# Sheet_v1.net
KiCad netlist of a schematic drawn in Altium Designer
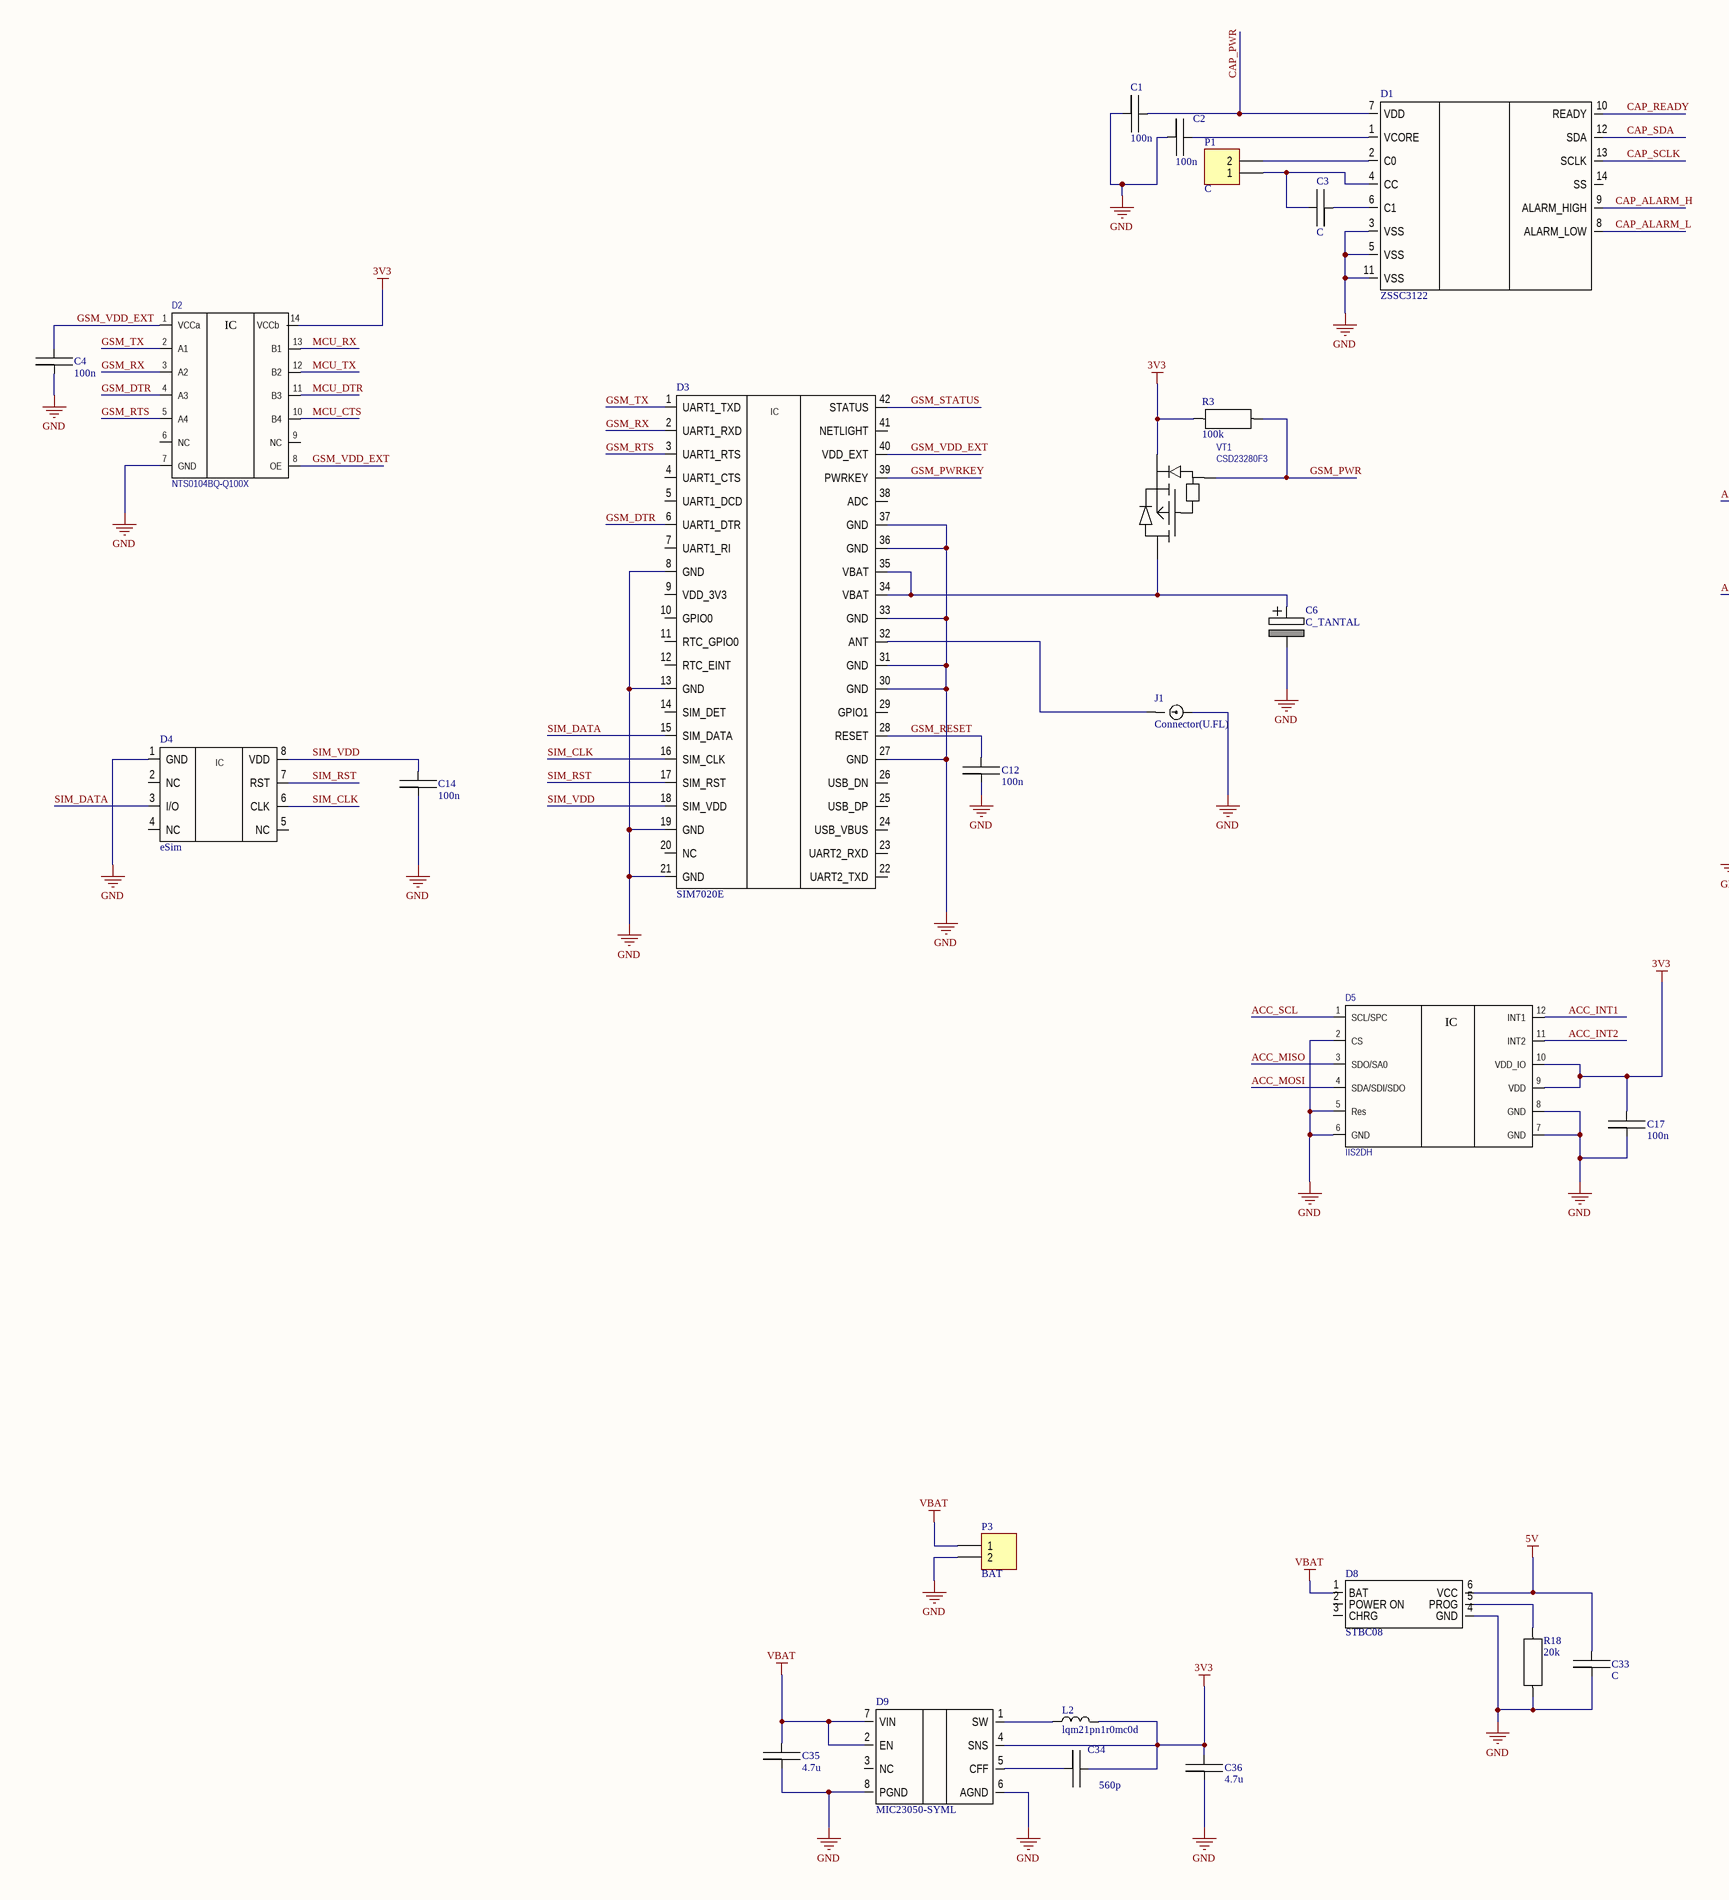
[diagram p0: Sheet_v1.SchDoc, left]
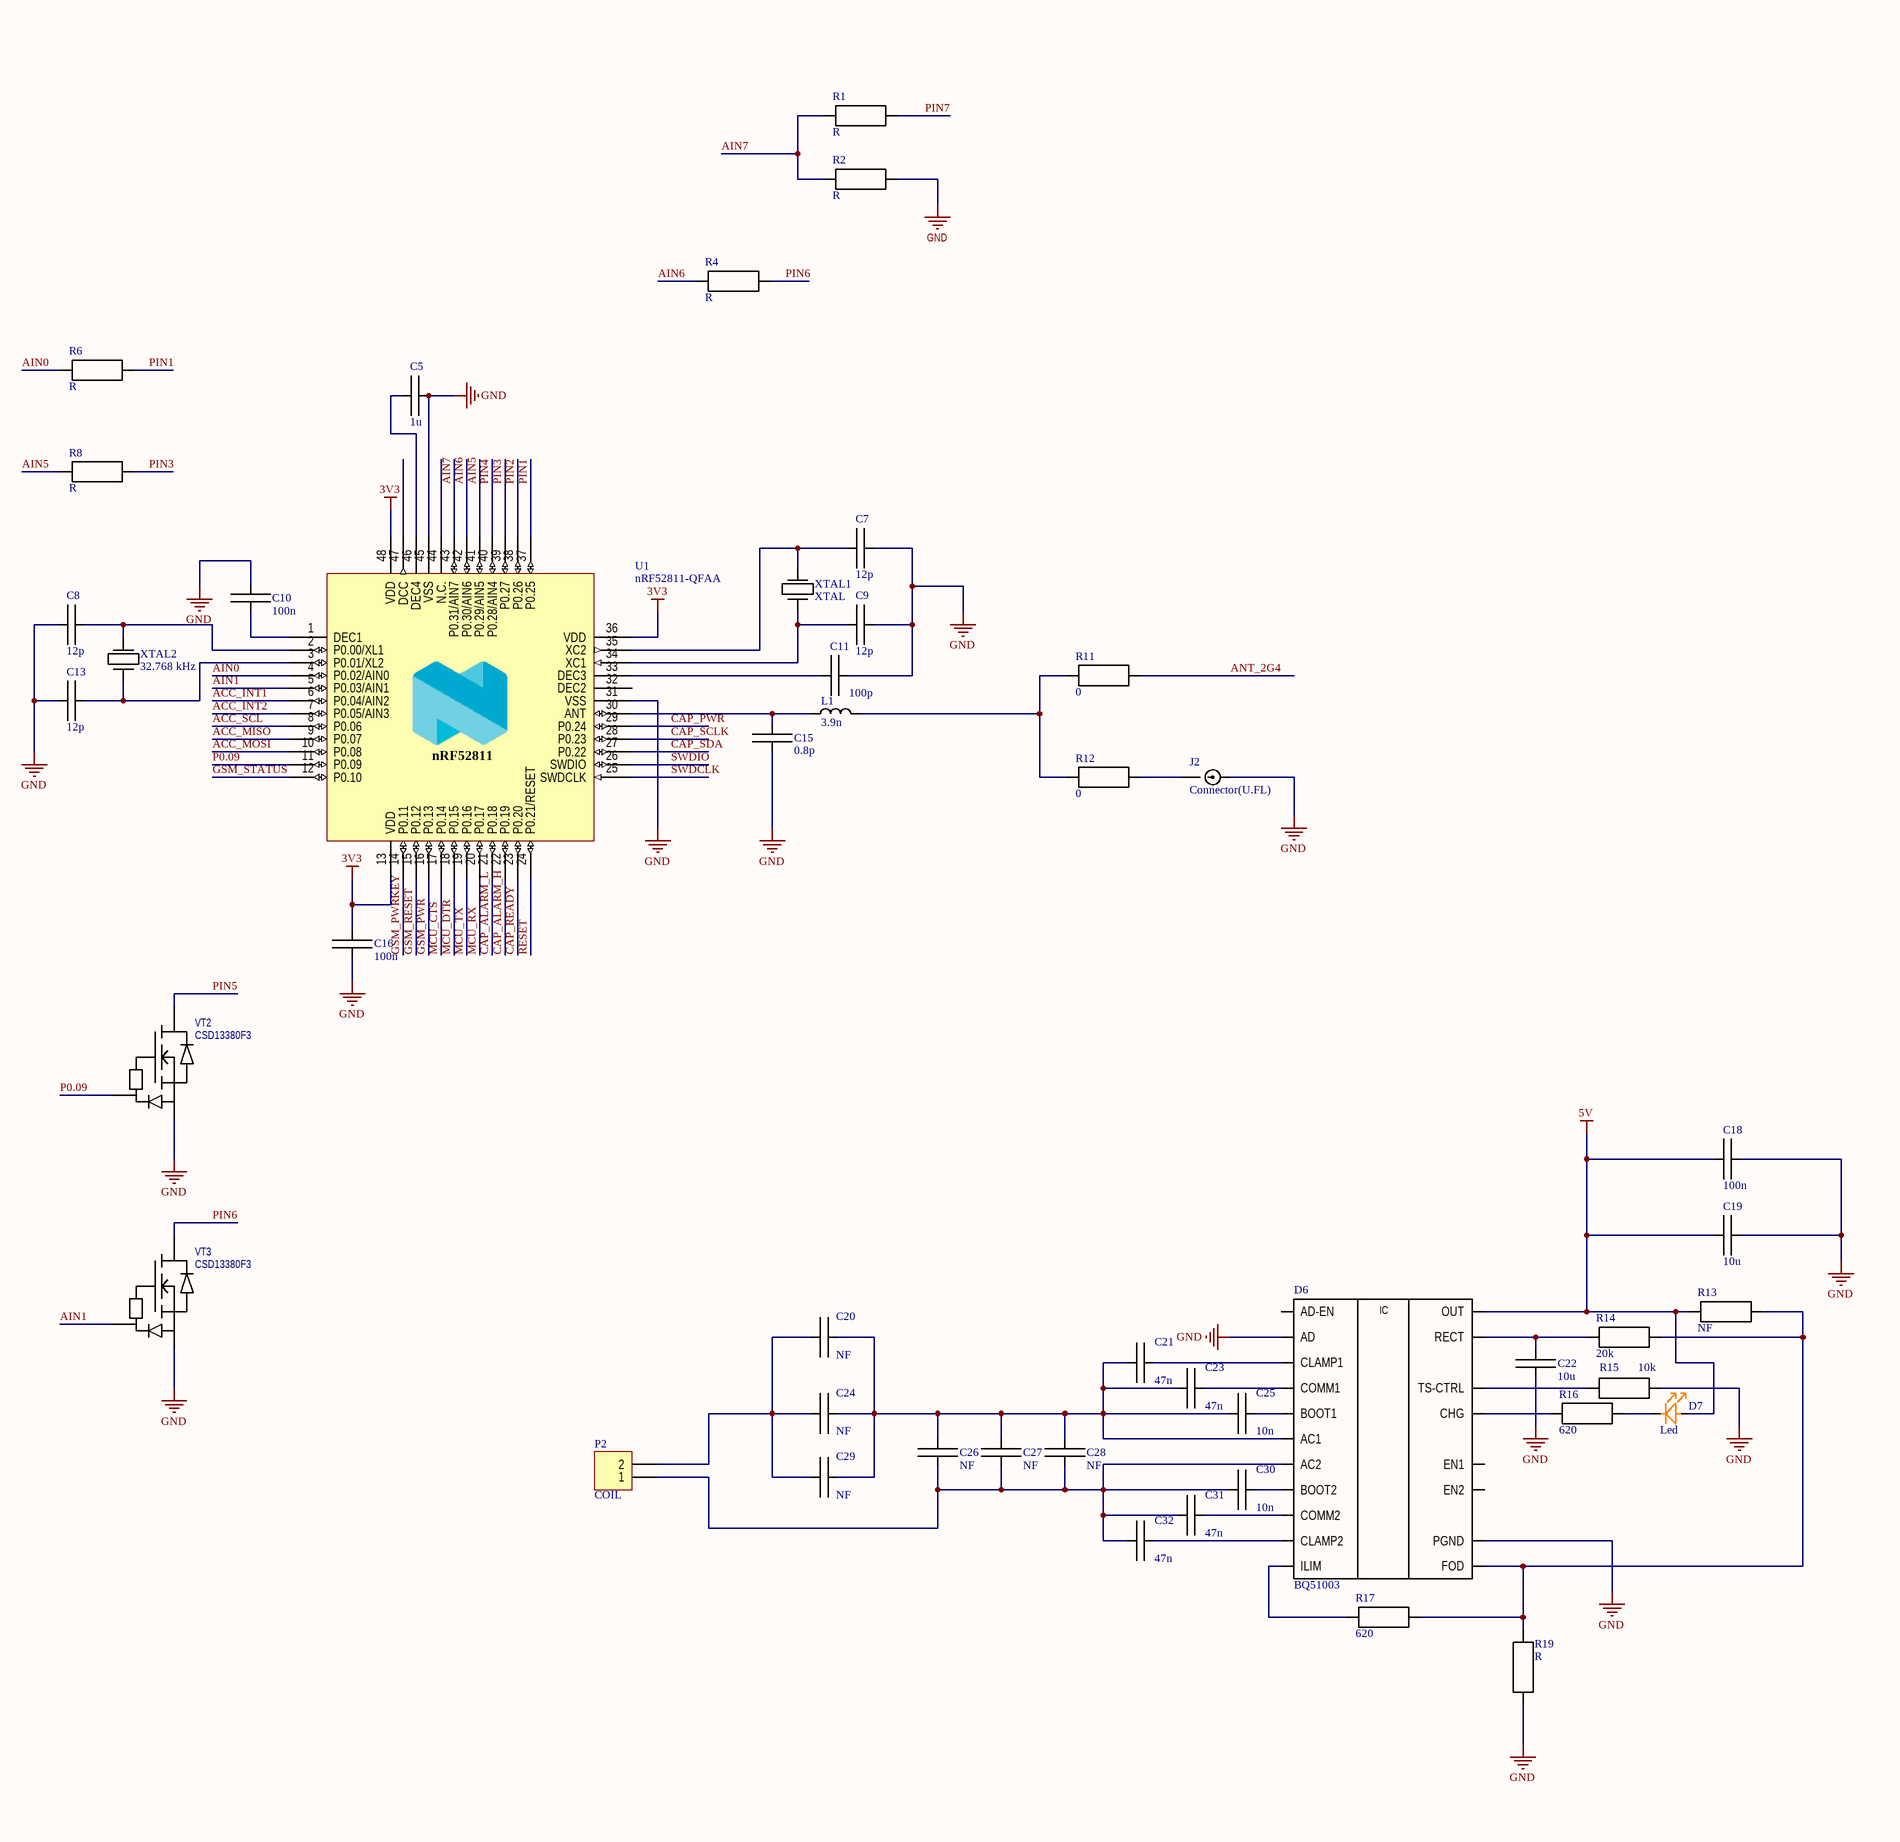
[diagram p1: Sheet_v1.SchDoc, right]

(export (version "E")
  (design (tool "Eeschema 10.0.6"))
  (components
    (comp (ref "C1") (value "100n") (footprint "C0402") (libsource (lib "Schlib1") (part "C")))
    (comp (ref "C2") (value "100n") (footprint "C0402") (libsource (lib "Schlib1") (part "C")))
    (comp (ref "C3") (value "C") (footprint "C0402") (libsource (lib "Schlib1") (part "C")))
    (comp (ref "C4") (value "100n") (footprint "C0402") (libsource (lib "Schlib1") (part "C")))
    (comp (ref "C5") (value "1u") (footprint "C0402") (libsource (lib "Schlib1") (part "C")))
    (comp (ref "C6") (value "C_TANTAL") (footprint "C_TYPE_D") (libsource (lib "Schlib1") (part "C_TANTAL")))
    (comp (ref "C7") (value "12p") (footprint "C0402") (libsource (lib "Schlib1") (part "C")))
    (comp (ref "C8") (value "12p") (footprint "C0402") (libsource (lib "Schlib1") (part "C")))
    (comp (ref "C9") (value "12p") (footprint "C0402") (libsource (lib "Schlib1") (part "C")))
    (comp (ref "C10") (value "100n") (footprint "C0402") (libsource (lib "Schlib1") (part "C")))
    (comp (ref "C11") (value "100p") (footprint "C0402") (libsource (lib "Schlib1") (part "C")))
    (comp (ref "C12") (value "100n") (footprint "C0402") (libsource (lib "Schlib1") (part "C")))
    (comp (ref "C13") (value "12p") (footprint "C0402") (libsource (lib "Schlib1") (part "C")))
    (comp (ref "C14") (value "100n") (footprint "C0402") (libsource (lib "Schlib1") (part "C")))
    (comp (ref "C15") (value "0.8p") (footprint "C0402") (libsource (lib "Schlib1") (part "C")))
    (comp (ref "C16") (value "100n") (footprint "C0402") (libsource (lib "Schlib1") (part "C")))
    (comp (ref "C17") (value "100n") (footprint "C0402") (libsource (lib "Schlib1") (part "C")))
    (comp (ref "C18") (value "100n") (footprint "C0402") (libsource (lib "Schlib1") (part "C")))
    (comp (ref "C19") (value "10u") (footprint "C0603") (libsource (lib "Schlib1") (part "C")))
    (comp (ref "C20") (value "NF") (footprint "C0603") (libsource (lib "Schlib1") (part "C")))
    (comp (ref "C21") (value "47n") (footprint "C0603") (libsource (lib "Schlib1") (part "C")))
    (comp (ref "C22") (value "10u") (footprint "C0402") (libsource (lib "Schlib1") (part "C")))
    (comp (ref "C23") (value "47n") (footprint "C0603") (libsource (lib "Schlib1") (part "C")))
    (comp (ref "C24") (value "NF") (footprint "C0603") (libsource (lib "Schlib1") (part "C")))
    (comp (ref "C25") (value "10n") (footprint "C0603") (libsource (lib "Schlib1") (part "C")))
    (comp (ref "C26") (value "NF") (footprint "C0603") (libsource (lib "Schlib1") (part "C")))
    (comp (ref "C27") (value "NF") (footprint "C0603") (libsource (lib "Schlib1") (part "C")))
    (comp (ref "C28") (value "NF") (footprint "C0603") (libsource (lib "Schlib1") (part "C")))
    (comp (ref "C29") (value "NF") (footprint "C0603") (libsource (lib "Schlib1") (part "C")))
    (comp (ref "C30") (value "10n") (footprint "C0603") (libsource (lib "Schlib1") (part "C")))
    (comp (ref "C31") (value "47n") (footprint "C0603") (libsource (lib "Schlib1") (part "C")))
    (comp (ref "C32") (value "47n") (footprint "C0603") (libsource (lib "Schlib1") (part "C")))
    (comp (ref "C33") (value "C") (footprint "C0402") (libsource (lib "Schlib1") (part "C")))
    (comp (ref "C34") (value "560p") (footprint "C0402") (libsource (lib "Schlib1") (part "C")))
    (comp (ref "C35") (value "4.7u") (footprint "C0805") (libsource (lib "Schlib1") (part "C")))
    (comp (ref "C36") (value "4.7u") (footprint "C0805") (libsource (lib "Schlib1") (part "C")))
    (comp (ref "D1") (value "ZSSC3122") (footprint "TSSOP14") (libsource (lib "Schlib1") (part "ZSSC3122")))
    (comp (ref "D2")
      (value "NTS0104BQ-Q100X")
      (footprint "DHVQFN14")
      (libsource (lib "Schlib1") (part "NTS0304"))
    )
    (comp (ref "D3") (value "SIM7020E") (footprint "SIM7020E") (libsource (lib "Schlib1") (part "SIM7020E")))
    (comp (ref "D4") (value "eSim") (footprint "VQFN8") (libsource (lib "Schlib1") (part "eSim")))
    (comp (ref "D5") (value "IIS2DH") (footprint "LGA12") (libsource (lib "Schlib1") (part "IIS2DH")))
    (comp (ref "D6") (value "BQ51003") (footprint "DSBGA") (libsource (lib "Schlib1") (part "BQ51003")))
    (comp (ref "D7") (value "Led") (footprint "D0402(1006)") (libsource (lib "Schlib1") (part "Led")))
    (comp (ref "D8") (value "STBC08") (footprint "DFN6") (libsource (lib "Schlib1") (part "STBC08")))
    (comp (ref "D9")
      (value "MIC23050-SYML")
      (footprint "MLF8")
      (libsource (lib "Schlib1") (part "MIC23050-SYML"))
    )
    (comp (ref "J1")
      (value "Connector(U.FL)")
      (footprint "U.FL")
      (libsource (lib "Schlib1") (part "Connector(U.FL)"))
    )
    (comp (ref "J2")
      (value "Connector(U.FL)")
      (footprint "U.FL")
      (libsource (lib "Schlib1") (part "Connector(U.FL)"))
    )
    (comp (ref "L1") (value "3.9n") (footprint "L0402") (libsource (lib "Schlib1") (part "L")))
    (comp (ref "L2") (value "lqm21pn1r0mc0d") (footprint "L0805") (libsource (lib "Schlib1") (part "L")))
    (comp (ref "P1")
      (value "C")
      (footprint "HDR1X2")
      (description "Header, 2-Pin")
      (fields (field (name "PUBLISHER") "Altium Limited"))
      (libsource (lib "Miscellaneous Connectors") (part "Header 2"))
    )
    (comp (ref "P2")
      (value "COIL")
      (footprint "HDR1X2")
      (description "Header, 2-Pin")
      (fields (field (name "PUBLISHER") "Altium Limited"))
      (libsource (lib "Miscellaneous Connectors") (part "Header 2"))
    )
    (comp (ref "P3")
      (value "BAT")
      (footprint "HDR1X2")
      (description "Header, 2-Pin")
      (fields (field (name "PUBLISHER") "Altium Limited"))
      (libsource (lib "") (part "Header 2_1"))
    )
    (comp (ref "R1") (value "R") (footprint "R0402") (libsource (lib "Schlib1") (part "R")))
    (comp (ref "R2") (value "R") (footprint "R0402") (libsource (lib "Schlib1") (part "R")))
    (comp (ref "R3") (value "100k") (footprint "R0402") (libsource (lib "Schlib1") (part "R")))
    (comp (ref "R4") (value "R") (footprint "R0402") (libsource (lib "Schlib1") (part "R")))
    (comp (ref "R6") (value "R") (footprint "R0402") (libsource (lib "Schlib1") (part "R")))
    (comp (ref "R8") (value "R") (footprint "R0402") (libsource (lib "Schlib1") (part "R")))
    (comp (ref "R11") (value "0") (footprint "R0402") (libsource (lib "Schlib1") (part "R")))
    (comp (ref "R12") (value "0") (footprint "R0402") (libsource (lib "Schlib1") (part "R")))
    (comp (ref "R13") (value "NF") (footprint "R0402") (libsource (lib "Schlib1") (part "R")))
    (comp (ref "R14") (value "20k") (footprint "R0402") (libsource (lib "Schlib1") (part "R")))
    (comp (ref "R15") (value "10k") (footprint "R0402") (libsource (lib "Schlib1") (part "R")))
    (comp (ref "R16") (value "620") (footprint "R0402") (libsource (lib "Schlib1") (part "R")))
    (comp (ref "R17") (value "620") (footprint "R0402") (libsource (lib "Schlib1") (part "R")))
    (comp (ref "R18") (value "20k") (footprint "R0402") (libsource (lib "Schlib1") (part "R")))
    (comp (ref "R19") (value "R") (footprint "R0402") (libsource (lib "Schlib1") (part "R")))
    (comp (ref "U1")
      (value "nRF52811-QFAA")
      (footprint "QFN40P600X600X90-48N")
      (description "Multi-protocol Bluetooth Low Energy, IEEE 802.15.4, ANT and 2.4GHz proprietary system-on-chip")
      (fields
        (field (name "PART NUMBER") "nRF52811-QFAAA0")
        (field (name "MANUFACTURER") "Nordic Semiconductor")
        (field (name "PUBLISHER") "Nordic Semiconductor")
      )
      (libsource (lib "nrf52811_qxaa") (part "nRF52811_QFAA"))
    )
    (comp (ref "VT1")
      (value "CSD23280F3")
      (footprint "CSD13380F3")
      (libsource (lib "Schlib1") (part "CSD23280F3"))
    )
    (comp (ref "VT2")
      (value "CSD13380F3")
      (footprint "CSD13380F3")
      (libsource (lib "Schlib1") (part "CSD13380F3"))
    )
    (comp (ref "VT3")
      (value "CSD13380F3")
      (footprint "CSD13380F3")
      (libsource (lib "Schlib1") (part "CSD13380F3"))
    )
    (comp (ref "XTAL1") (value "XTAL") (footprint "NX2016SA") (libsource (lib "Schlib1") (part "XTAL")))
    (comp (ref "XTAL2")
      (value "32.768 kHz")
      (footprint "NX2012SA")
      (libsource (lib "Schlib1") (part "32.768 kHz"))
    )
  )
  (nets
    (net (code "1") (name "/ACC_INT1") (class "Default")
      (node (ref "D5") (pin "12") (pinfunction "INT1_12") (pintype "passive"))
      (node (ref "U1") (pin "6") (pinfunction "P0.04/AIN2_6") (pintype "bidirectional"))
    )
    (net (code "2") (name "/ACC_INT2") (class "Default")
      (node (ref "D5") (pin "11") (pinfunction "INT2_11") (pintype "passive"))
      (node (ref "U1") (pin "7") (pinfunction "P0.05/AIN3_7") (pintype "bidirectional"))
    )
    (net (code "3") (name "/ACC_MISO") (class "Default")
      (node (ref "D5") (pin "3") (pinfunction "SDO/SA0_3") (pintype "passive"))
      (node (ref "U1") (pin "9") (pinfunction "P0.07_9") (pintype "bidirectional"))
    )
    (net (code "4") (name "/ACC_MOSI") (class "Default")
      (node (ref "D5") (pin "4") (pinfunction "SDA/SDI/SDO_4") (pintype "passive"))
      (node (ref "U1") (pin "10") (pinfunction "P0.08_10") (pintype "bidirectional"))
    )
    (net (code "5") (name "/ACC_SCL") (class "Default")
      (node (ref "D5") (pin "1") (pinfunction "SCL/SPC_1") (pintype "passive"))
      (node (ref "U1") (pin "8") (pinfunction "P0.06_8") (pintype "bidirectional"))
    )
    (net (code "6") (name "/AIN0") (class "Default")
      (node (ref "R6") (pin "1") (pinfunction "1_1") (pintype "passive"))
      (node (ref "U1") (pin "4") (pinfunction "P0.02/AIN0_4") (pintype "bidirectional"))
    )
    (net (code "7") (name "/AIN1") (class "Default")
      (node (ref "U1") (pin "5") (pinfunction "P0.03/AIN1_5") (pintype "bidirectional"))
      (node (ref "VT3") (pin "G") (pinfunction "G_G") (pintype "passive"))
    )
    (net (code "8") (name "/AIN5") (class "Default")
      (node (ref "R8") (pin "1") (pinfunction "1_1") (pintype "passive"))
      (node (ref "U1") (pin "41") (pinfunction "P0.29/AIN5_41") (pintype "bidirectional"))
    )
    (net (code "9") (name "/AIN6") (class "Default")
      (node (ref "R4") (pin "1") (pinfunction "1_1") (pintype "passive"))
      (node (ref "U1") (pin "42") (pinfunction "P0.30/AIN6_42") (pintype "bidirectional"))
    )
    (net (code "10") (name "/AIN7") (class "Default")
      (node (ref "R1") (pin "1") (pinfunction "1_1") (pintype "passive"))
      (node (ref "R2") (pin "1") (pinfunction "1_1") (pintype "passive"))
      (node (ref "U1") (pin "43") (pinfunction "P0.31/AIN7_43") (pintype "bidirectional"))
    )
    (net (code "11") (name "/ANT_2G4") (class "Default")
      (node (ref "R11") (pin "2") (pinfunction "2_2") (pintype "passive"))
    )
    (net (code "12") (name "/CAP_ALARM_H") (class "Default")
      (node (ref "D1") (pin "9") (pinfunction "ALARM_HIGH_9") (pintype "passive"))
      (node (ref "U1") (pin "22") (pinfunction "P0.19_22") (pintype "bidirectional"))
    )
    (net (code "13") (name "/CAP_ALARM_L") (class "Default")
      (node (ref "D1") (pin "8") (pinfunction "ALARM_LOW_8") (pintype "passive"))
      (node (ref "U1") (pin "21") (pinfunction "P0.18_21") (pintype "bidirectional"))
    )
    (net (code "14") (name "/CAP_PWR") (class "Default")
      (node (ref "C1") (pin "2") (pinfunction "2_2") (pintype "passive"))
      (node (ref "D1") (pin "7") (pinfunction "VDD_7") (pintype "passive"))
      (node (ref "U1") (pin "29") (pinfunction "P0.24_29") (pintype "bidirectional"))
    )
    (net (code "15") (name "/CAP_READY") (class "Default")
      (node (ref "D1") (pin "10") (pinfunction "READY_10") (pintype "passive"))
      (node (ref "U1") (pin "23") (pinfunction "P0.20_23") (pintype "bidirectional"))
    )
    (net (code "16") (name "/CAP_SCLK") (class "Default")
      (node (ref "D1") (pin "13") (pinfunction "SCLK_13") (pintype "passive"))
      (node (ref "U1") (pin "28") (pinfunction "P0.23_28") (pintype "bidirectional"))
    )
    (net (code "17") (name "/CAP_SDA") (class "Default")
      (node (ref "D1") (pin "12") (pinfunction "SDA_12") (pintype "passive"))
      (node (ref "U1") (pin "27") (pinfunction "P0.22_27") (pintype "bidirectional"))
    )
    (net (code "18") (name "/GSM_DTR") (class "Default")
      (node (ref "D2") (pin "4") (pinfunction "A3_4") (pintype "passive"))
      (node (ref "D3") (pin "6") (pinfunction "UART1_DTR_6") (pintype "passive"))
    )
    (net (code "19") (name "/GSM_PWR") (class "Default")
      (node (ref "R3") (pin "2") (pinfunction "2_2") (pintype "passive"))
      (node (ref "U1") (pin "16") (pinfunction "P0.13_16") (pintype "bidirectional"))
      (node (ref "VT1") (pin "G") (pinfunction "G_G") (pintype "passive"))
    )
    (net (code "20") (name "/GSM_PWRKEY") (class "Default")
      (node (ref "D3") (pin "39") (pinfunction "PWRKEY_39") (pintype "passive"))
      (node (ref "U1") (pin "14") (pinfunction "P0.11_14") (pintype "bidirectional"))
    )
    (net (code "21") (name "/GSM_RESET") (class "Default")
      (node (ref "C12") (pin "2") (pinfunction "2_2") (pintype "passive"))
      (node (ref "D3") (pin "28") (pinfunction "RESET_28") (pintype "passive"))
      (node (ref "U1") (pin "15") (pinfunction "P0.12_15") (pintype "bidirectional"))
    )
    (net (code "22") (name "/GSM_RTS") (class "Default")
      (node (ref "D2") (pin "5") (pinfunction "A4_5") (pintype "passive"))
      (node (ref "D3") (pin "3") (pinfunction "UART1_RTS_3") (pintype "passive"))
    )
    (net (code "23") (name "/GSM_RX") (class "Default")
      (node (ref "D2") (pin "3") (pinfunction "A2_3") (pintype "passive"))
      (node (ref "D3") (pin "2") (pinfunction "UART1_RXD_2") (pintype "passive"))
    )
    (net (code "24") (name "/GSM_STATUS") (class "Default")
      (node (ref "D3") (pin "42") (pinfunction "STATUS_42") (pintype "passive"))
      (node (ref "U1") (pin "12") (pinfunction "P0.10_12") (pintype "bidirectional"))
    )
    (net (code "25") (name "/GSM_TX") (class "Default")
      (node (ref "D2") (pin "2") (pinfunction "A1_2") (pintype "passive"))
      (node (ref "D3") (pin "1") (pinfunction "UART1_TXD_1") (pintype "passive"))
    )
    (net (code "26") (name "/GSM_VDD_EXT") (class "Default")
      (node (ref "C4") (pin "2") (pinfunction "2_2") (pintype "passive"))
      (node (ref "D2") (pin "1") (pinfunction "VCCa_1") (pintype "passive"))
      (node (ref "D2") (pin "8") (pinfunction "OE_8") (pintype "passive"))
      (node (ref "D3") (pin "40") (pinfunction "VDD_EXT_40") (pintype "passive"))
    )
    (net (code "27") (name "/MCU_CTS") (class "Default")
      (node (ref "D2") (pin "10") (pinfunction "B4_10") (pintype "passive"))
      (node (ref "U1") (pin "17") (pinfunction "P0.14_17") (pintype "bidirectional"))
    )
    (net (code "28") (name "/MCU_DTR") (class "Default")
      (node (ref "D2") (pin "11") (pinfunction "B3_11") (pintype "passive"))
      (node (ref "U1") (pin "18") (pinfunction "P0.15_18") (pintype "bidirectional"))
    )
    (net (code "29") (name "/MCU_RX") (class "Default")
      (node (ref "D2") (pin "13") (pinfunction "B1_13") (pintype "passive"))
      (node (ref "U1") (pin "20") (pinfunction "P0.17_20") (pintype "bidirectional"))
    )
    (net (code "30") (name "/MCU_TX") (class "Default")
      (node (ref "D2") (pin "12") (pinfunction "B2_12") (pintype "passive"))
      (node (ref "U1") (pin "19") (pinfunction "P0.16_19") (pintype "bidirectional"))
    )
    (net (code "31") (name "/P0.09") (class "Default")
      (node (ref "U1") (pin "11") (pinfunction "P0.09_11") (pintype "bidirectional"))
      (node (ref "VT2") (pin "G") (pinfunction "G_G") (pintype "passive"))
    )
    (net (code "32") (name "/PIN1") (class "Default")
      (node (ref "R6") (pin "2") (pinfunction "2_2") (pintype "passive"))
      (node (ref "U1") (pin "37") (pinfunction "P0.25_37") (pintype "bidirectional"))
    )
    (net (code "33") (name "/PIN2") (class "Default")
      (node (ref "U1") (pin "38") (pinfunction "P0.26_38") (pintype "bidirectional"))
    )
    (net (code "34") (name "/PIN3") (class "Default")
      (node (ref "R8") (pin "2") (pinfunction "2_2") (pintype "passive"))
      (node (ref "U1") (pin "39") (pinfunction "P0.27_39") (pintype "bidirectional"))
    )
    (net (code "35") (name "/PIN4") (class "Default")
      (node (ref "U1") (pin "40") (pinfunction "P0.28/AIN4_40") (pintype "bidirectional"))
    )
    (net (code "36") (name "/PIN5") (class "Default")
      (node (ref "VT2") (pin "D") (pinfunction "D_D") (pintype "passive"))
    )
    (net (code "37") (name "/PIN6") (class "Default")
      (node (ref "R4") (pin "2") (pinfunction "2_2") (pintype "passive"))
      (node (ref "VT3") (pin "D") (pinfunction "D_D") (pintype "passive"))
    )
    (net (code "38") (name "/PIN7") (class "Default")
      (node (ref "R1") (pin "2") (pinfunction "2_2") (pintype "passive"))
    )
    (net (code "39") (name "/RESET") (class "Default")
      (node (ref "U1") (pin "24") (pinfunction "P0.21/RESET_24") (pintype "bidirectional"))
    )
    (net (code "40") (name "/SIM_CLK") (class "Default")
      (node (ref "D3") (pin "16") (pinfunction "SIM_CLK_16") (pintype "passive"))
      (node (ref "D4") (pin "6") (pinfunction "CLK_6") (pintype "passive"))
    )
    (net (code "41") (name "/SIM_DATA") (class "Default")
      (node (ref "D3") (pin "15") (pinfunction "SIM_DATA_15") (pintype "passive"))
      (node (ref "D4") (pin "3") (pinfunction "I/O_3") (pintype "passive"))
    )
    (net (code "42") (name "/SIM_RST") (class "Default")
      (node (ref "D3") (pin "17") (pinfunction "SIM_RST_17") (pintype "passive"))
      (node (ref "D4") (pin "7") (pinfunction "RST_7") (pintype "passive"))
    )
    (net (code "43") (name "/SIM_VDD") (class "Default")
      (node (ref "C14") (pin "2") (pinfunction "2_2") (pintype "passive"))
      (node (ref "D3") (pin "18") (pinfunction "SIM_VDD_18") (pintype "passive"))
      (node (ref "D4") (pin "8") (pinfunction "VDD_8") (pintype "passive"))
    )
    (net (code "44") (name "/SWDCLK") (class "Default")
      (node (ref "U1") (pin "25") (pinfunction "SWDCLK_25") (pintype "input"))
    )
    (net (code "45") (name "/SWDIO") (class "Default")
      (node (ref "U1") (pin "26") (pinfunction "SWDIO_26") (pintype "bidirectional"))
    )
    (net (code "46") (name "3V3") (class "Default")
      (node (ref "C16") (pin "2") (pinfunction "2_2") (pintype "passive"))
      (node (ref "C17") (pin "2") (pinfunction "2_2") (pintype "passive"))
      (node (ref "C34") (pin "2") (pinfunction "2_2") (pintype "passive"))
      (node (ref "C36") (pin "2") (pinfunction "2_2") (pintype "passive"))
      (node (ref "D2") (pin "14") (pinfunction "VCCb_14") (pintype "passive"))
      (node (ref "D5") (pin "10") (pinfunction "VDD_IO_10") (pintype "passive"))
      (node (ref "D5") (pin "9") (pinfunction "VDD_9") (pintype "passive"))
      (node (ref "D9") (pin "4") (pinfunction "SNS_4") (pintype "passive"))
      (node (ref "L2") (pin "2") (pinfunction "2_2") (pintype "passive"))
      (node (ref "R3") (pin "1") (pinfunction "1_1") (pintype "passive"))
      (node (ref "U1") (pin "13") (pinfunction "VDD_13") (pintype "power_in"))
      (node (ref "U1") (pin "36") (pinfunction "VDD_36") (pintype "power_in"))
      (node (ref "U1") (pin "48") (pinfunction "VDD_48") (pintype "power_in"))
      (node (ref "VT1") (pin "S") (pinfunction "S_S") (pintype "passive"))
    )
    (net (code "47") (name "5V") (class "Default")
      (node (ref "C18") (pin "1") (pinfunction "1_1") (pintype "passive"))
      (node (ref "C19") (pin "2") (pinfunction "2_2") (pintype "passive"))
      (node (ref "C33") (pin "2") (pinfunction "2_2") (pintype "passive"))
      (node (ref "D6") (pin "OUT") (pinfunction "OUT_OUT") (pintype "passive"))
      (node (ref "D7") (pin "2") (pinfunction "2_2") (pintype "passive"))
      (node (ref "D8") (pin "6") (pinfunction "VCC_6") (pintype "passive"))
      (node (ref "R13") (pin "1") (pinfunction "1_1") (pintype "passive"))
    )
    (net (code "48") (name "GND") (class "Default")
      (node (ref "C1") (pin "1") (pinfunction "1_1") (pintype "passive"))
      (node (ref "C10") (pin "2") (pinfunction "2_2") (pintype "passive"))
      (node (ref "C11") (pin "2") (pinfunction "2_2") (pintype "passive"))
      (node (ref "C12") (pin "1") (pinfunction "1_1") (pintype "passive"))
      (node (ref "C13") (pin "1") (pinfunction "1_1") (pintype "passive"))
      (node (ref "C14") (pin "1") (pinfunction "1_1") (pintype "passive"))
      (node (ref "C15") (pin "1") (pinfunction "1_1") (pintype "passive"))
      (node (ref "C16") (pin "1") (pinfunction "1_1") (pintype "passive"))
      (node (ref "C17") (pin "1") (pinfunction "1_1") (pintype "passive"))
      (node (ref "C18") (pin "2") (pinfunction "2_2") (pintype "passive"))
      (node (ref "C19") (pin "1") (pinfunction "1_1") (pintype "passive"))
      (node (ref "C2") (pin "1") (pinfunction "1_1") (pintype "passive"))
      (node (ref "C22") (pin "1") (pinfunction "1_1") (pintype "passive"))
      (node (ref "C33") (pin "1") (pinfunction "1_1") (pintype "passive"))
      (node (ref "C35") (pin "1") (pinfunction "1_1") (pintype "passive"))
      (node (ref "C36") (pin "1") (pinfunction "1_1") (pintype "passive"))
      (node (ref "C4") (pin "1") (pinfunction "1_1") (pintype "passive"))
      (node (ref "C5") (pin "2") (pinfunction "2_2") (pintype "passive"))
      (node (ref "C6") (pin "2") (pinfunction "2_2") (pintype "passive"))
      (node (ref "C7") (pin "2") (pinfunction "2_2") (pintype "passive"))
      (node (ref "C8") (pin "1") (pinfunction "1_1") (pintype "passive"))
      (node (ref "C9") (pin "2") (pinfunction "2_2") (pintype "passive"))
      (node (ref "D1") (pin "11") (pinfunction "VSS_11") (pintype "passive"))
      (node (ref "D1") (pin "3") (pinfunction "VSS_3") (pintype "passive"))
      (node (ref "D1") (pin "5") (pinfunction "VSS_5") (pintype "passive"))
      (node (ref "D2") (pin "7") (pinfunction "GND_7") (pintype "passive"))
      (node (ref "D3") (pin "13") (pinfunction "GND_13") (pintype "passive"))
      (node (ref "D3") (pin "19") (pinfunction "GND_19") (pintype "passive"))
      (node (ref "D3") (pin "21") (pinfunction "GND_21") (pintype "passive"))
      (node (ref "D3") (pin "27") (pinfunction "GND_27") (pintype "passive"))
      (node (ref "D3") (pin "30") (pinfunction "GND_30") (pintype "passive"))
      (node (ref "D3") (pin "31") (pinfunction "GND_31") (pintype "passive"))
      (node (ref "D3") (pin "33") (pinfunction "GND_33") (pintype "passive"))
      (node (ref "D3") (pin "36") (pinfunction "GND_36") (pintype "passive"))
      (node (ref "D3") (pin "37") (pinfunction "GND_37") (pintype "passive"))
      (node (ref "D3") (pin "8") (pinfunction "GND_8") (pintype "passive"))
      (node (ref "D4") (pin "1") (pinfunction "GND_1") (pintype "passive"))
      (node (ref "D5") (pin "2") (pinfunction "CS_2") (pintype "passive"))
      (node (ref "D5") (pin "5") (pinfunction "Res_5") (pintype "passive"))
      (node (ref "D5") (pin "6") (pinfunction "GND_6") (pintype "passive"))
      (node (ref "D5") (pin "7") (pinfunction "GND_7") (pintype "passive"))
      (node (ref "D5") (pin "8") (pinfunction "GND_8") (pintype "passive"))
      (node (ref "D6") (pin "AD") (pinfunction "AD_AD") (pintype "passive"))
      (node (ref "D6") (pin "PGND") (pinfunction "PGND_PGND") (pintype "passive"))
      (node (ref "D8") (pin "4") (pinfunction "GND_4") (pintype "passive"))
      (node (ref "D9") (pin "6") (pinfunction "AGND_6") (pintype "passive"))
      (node (ref "D9") (pin "8") (pinfunction "PGND_8") (pintype "passive"))
      (node (ref "J1") (pin "2") (pinfunction "2_2") (pintype "passive"))
      (node (ref "J2") (pin "2") (pinfunction "2_2") (pintype "passive"))
      (node (ref "P3") (pin "2") (pinfunction "2_2") (pintype "passive"))
      (node (ref "R15") (pin "1") (pinfunction "1_1") (pintype "passive"))
      (node (ref "R18") (pin "1") (pinfunction "1_1") (pintype "passive"))
      (node (ref "R19") (pin "1") (pinfunction "1_1") (pintype "passive"))
      (node (ref "R2") (pin "2") (pinfunction "2_2") (pintype "passive"))
      (node (ref "U1") (pin "31") (pinfunction "VSS_31") (pintype "power_in"))
      (node (ref "U1") (pin "45") (pinfunction "VSS_45") (pintype "power_in"))
      (node (ref "U1") (pin "49") (pinfunction "GND_49") (pintype "power_in"))
      (node (ref "VT2") (pin "S") (pinfunction "S_S") (pintype "passive"))
      (node (ref "VT3") (pin "S") (pinfunction "S_S") (pintype "passive"))
    )
    (net (code "49") (name "Net-(C6-Pad1)") (class "Default")
      (node (ref "C6") (pin "1") (pinfunction "1_1") (pintype "passive"))
      (node (ref "D3") (pin "34") (pinfunction "VBAT_34") (pintype "passive"))
      (node (ref "D3") (pin "35") (pinfunction "VBAT_35") (pintype "passive"))
      (node (ref "VT1") (pin "D") (pinfunction "D_D") (pintype "passive"))
    )
    (net (code "50") (name "Net-(C20-Pad1)") (class "Default")
      (node (ref "C20") (pin "1") (pinfunction "1_1") (pintype "passive"))
      (node (ref "C21") (pin "1") (pinfunction "1_1") (pintype "passive"))
      (node (ref "C23") (pin "1") (pinfunction "1_1") (pintype "passive"))
      (node (ref "C24") (pin "1") (pinfunction "1_1") (pintype "passive"))
      (node (ref "C25") (pin "1") (pinfunction "1_1") (pintype "passive"))
      (node (ref "C26") (pin "2") (pinfunction "2_2") (pintype "passive"))
      (node (ref "C27") (pin "2") (pinfunction "2_2") (pintype "passive"))
      (node (ref "C28") (pin "2") (pinfunction "2_2") (pintype "passive"))
      (node (ref "C29") (pin "1") (pinfunction "1_1") (pintype "passive"))
      (node (ref "D6") (pin "AC1") (pinfunction "AC1_AC1") (pintype "passive"))
    )
    (net (code "51") (name "Net-(C20-Pad2)") (class "Default")
      (node (ref "C20") (pin "2") (pinfunction "2_2") (pintype "passive"))
      (node (ref "C24") (pin "2") (pinfunction "2_2") (pintype "passive"))
      (node (ref "C29") (pin "2") (pinfunction "2_2") (pintype "passive"))
      (node (ref "P2") (pin "2") (pinfunction "2_2") (pintype "passive"))
    )
    (net (code "52") (name "Net-(C21-Pad2)") (class "Default")
      (node (ref "C21") (pin "2") (pinfunction "2_2") (pintype "passive"))
      (node (ref "D6") (pin "CLAMP1") (pinfunction "CLAMP1_CLAMP1") (pintype "passive"))
    )
    (net (code "53") (name "Net-(C22-Pad2)") (class "Default")
      (node (ref "C22") (pin "2") (pinfunction "2_2") (pintype "passive"))
      (node (ref "D6") (pin "RECT") (pinfunction "RECT_RECT") (pintype "passive"))
      (node (ref "R14") (pin "1") (pinfunction "1_1") (pintype "passive"))
    )
    (net (code "54") (name "Net-(C23-Pad2)") (class "Default")
      (node (ref "C23") (pin "2") (pinfunction "2_2") (pintype "passive"))
      (node (ref "D6") (pin "COMM1") (pinfunction "COMM1_COMM1") (pintype "passive"))
    )
    (net (code "55") (name "Net-(C25-Pad2)") (class "Default")
      (node (ref "C25") (pin "2") (pinfunction "2_2") (pintype "passive"))
      (node (ref "D6") (pin "BOOT1") (pinfunction "BOOT1_BOOT1") (pintype "passive"))
    )
    (net (code "56") (name "Net-(C26-Pad1)") (class "Default")
      (node (ref "C26") (pin "1") (pinfunction "1_1") (pintype "passive"))
      (node (ref "C27") (pin "1") (pinfunction "1_1") (pintype "passive"))
      (node (ref "C28") (pin "1") (pinfunction "1_1") (pintype "passive"))
      (node (ref "C30") (pin "1") (pinfunction "1_1") (pintype "passive"))
      (node (ref "C31") (pin "1") (pinfunction "1_1") (pintype "passive"))
      (node (ref "C32") (pin "1") (pinfunction "1_1") (pintype "passive"))
      (node (ref "D6") (pin "AC2") (pinfunction "AC2_AC2") (pintype "passive"))
      (node (ref "P2") (pin "1") (pinfunction "1_1") (pintype "passive"))
    )
    (net (code "57") (name "Net-(C30-Pad2)") (class "Default")
      (node (ref "C30") (pin "2") (pinfunction "2_2") (pintype "passive"))
      (node (ref "D6") (pin "BOOT2") (pinfunction "BOOT2_BOOT2") (pintype "passive"))
    )
    (net (code "58") (name "Net-(C31-Pad2)") (class "Default")
      (node (ref "C31") (pin "2") (pinfunction "2_2") (pintype "passive"))
      (node (ref "D6") (pin "COMM2") (pinfunction "COMM2_COMM2") (pintype "passive"))
    )
    (net (code "59") (name "Net-(C32-Pad2)") (class "Default")
      (node (ref "C32") (pin "2") (pinfunction "2_2") (pintype "passive"))
      (node (ref "D6") (pin "CLAMP2") (pinfunction "CLAMP2_CLAMP2") (pintype "passive"))
    )
    (net (code "60") (name "Net-(D1-C0)") (class "Default")
      (node (ref "D1") (pin "2") (pinfunction "C0_2") (pintype "passive"))
      (node (ref "P1") (pin "2") (pinfunction "2_2") (pintype "passive"))
    )
    (net (code "61") (name "Net-(D1-C1)") (class "Default")
      (node (ref "C3") (pin "1") (pinfunction "1_1") (pintype "passive"))
      (node (ref "D1") (pin "6") (pinfunction "C1_6") (pintype "passive"))
    )
    (net (code "62") (name "Net-(D1-CC)") (class "Default")
      (node (ref "C3") (pin "2") (pinfunction "2_2") (pintype "passive"))
      (node (ref "D1") (pin "4") (pinfunction "CC_4") (pintype "passive"))
      (node (ref "P1") (pin "1") (pinfunction "1_1") (pintype "passive"))
    )
    (net (code "63") (name "Net-(D1-VCORE)") (class "Default")
      (node (ref "C2") (pin "2") (pinfunction "2_2") (pintype "passive"))
      (node (ref "D1") (pin "1") (pinfunction "VCORE_1") (pintype "passive"))
    )
    (net (code "64") (name "Net-(D3-ANT)") (class "Default")
      (node (ref "D3") (pin "32") (pinfunction "ANT_32") (pintype "passive"))
      (node (ref "J1") (pin "1") (pinfunction "1_1") (pintype "passive"))
    )
    (net (code "65") (name "Net-(D6-PadCHG)") (class "Default")
      (node (ref "D6") (pin "CHG") (pinfunction "CHG_CHG") (pintype "passive"))
      (node (ref "R16") (pin "1") (pinfunction "1_1") (pintype "passive"))
    )
    (net (code "66") (name "Net-(D6-PadFOD)") (class "Default")
      (node (ref "D6") (pin "FOD") (pinfunction "FOD_FOD") (pintype "passive"))
      (node (ref "R13") (pin "2") (pinfunction "2_2") (pintype "passive"))
      (node (ref "R14") (pin "2") (pinfunction "2_2") (pintype "passive"))
      (node (ref "R17") (pin "2") (pinfunction "2_2") (pintype "passive"))
      (node (ref "R19") (pin "2") (pinfunction "2_2") (pintype "passive"))
    )
    (net (code "67") (name "Net-(D6-PadILIM)") (class "Default")
      (node (ref "D6") (pin "ILIM") (pinfunction "ILIM_ILIM") (pintype "passive"))
      (node (ref "R17") (pin "1") (pinfunction "1_1") (pintype "passive"))
    )
    (net (code "68") (name "Net-(D6-PadTS-CTRL)") (class "Default")
      (node (ref "D6") (pin "TS-CTRL") (pinfunction "TS-CTRL_TS-CTRL") (pintype "passive"))
      (node (ref "R15") (pin "2") (pinfunction "2_2") (pintype "passive"))
    )
    (net (code "69") (name "Net-(D7-Pad1)") (class "Default")
      (node (ref "D7") (pin "1") (pinfunction "1_1") (pintype "passive"))
      (node (ref "R16") (pin "2") (pinfunction "2_2") (pintype "passive"))
    )
    (net (code "70") (name "Net-(D8-PROG)") (class "Default")
      (node (ref "D8") (pin "5") (pinfunction "PROG_5") (pintype "passive"))
      (node (ref "R18") (pin "2") (pinfunction "2_2") (pintype "passive"))
    )
    (net (code "71") (name "Net-(D9-CFF)") (class "Default")
      (node (ref "C34") (pin "1") (pinfunction "1_1") (pintype "passive"))
      (node (ref "D9") (pin "5") (pinfunction "CFF_5") (pintype "passive"))
    )
    (net (code "72") (name "Net-(D9-SW)") (class "Default")
      (node (ref "D9") (pin "1") (pinfunction "SW_1") (pintype "passive"))
      (node (ref "L2") (pin "1") (pinfunction "1_1") (pintype "passive"))
    )
    (net (code "73") (name "Net-(J2-Pad1)") (class "Default")
      (node (ref "J2") (pin "1") (pinfunction "1_1") (pintype "passive"))
      (node (ref "R12") (pin "2") (pinfunction "2_2") (pintype "passive"))
    )
    (net (code "74") (name "Net-(L1-Pad2)") (class "Default")
      (node (ref "L1") (pin "2") (pinfunction "2_2") (pintype "passive"))
      (node (ref "R11") (pin "1") (pinfunction "1_1") (pintype "passive"))
      (node (ref "R12") (pin "1") (pinfunction "1_1") (pintype "passive"))
    )
    (net (code "75") (name "Net-(U1-ANT)") (class "Default")
      (node (ref "C15") (pin "2") (pinfunction "2_2") (pintype "passive"))
      (node (ref "L1") (pin "1") (pinfunction "1_1") (pintype "passive"))
      (node (ref "U1") (pin "30") (pinfunction "ANT_30") (pintype "bidirectional"))
    )
    (net (code "76") (name "Net-(U1-DEC1)") (class "Default")
      (node (ref "C10") (pin "1") (pinfunction "1_1") (pintype "passive"))
      (node (ref "U1") (pin "1") (pinfunction "DEC1_1") (pintype "power_in"))
    )
    (net (code "77") (name "Net-(U1-DEC3)") (class "Default")
      (node (ref "C11") (pin "1") (pinfunction "1_1") (pintype "passive"))
      (node (ref "U1") (pin "33") (pinfunction "DEC3_33") (pintype "power_in"))
    )
    (net (code "78") (name "Net-(U1-DEC4)") (class "Default")
      (node (ref "C5") (pin "1") (pinfunction "1_1") (pintype "passive"))
      (node (ref "U1") (pin "46") (pinfunction "DEC4_46") (pintype "power_in"))
    )
    (net (code "79") (name "Net-(U1-P0.00{slash}XL1)") (class "Default")
      (node (ref "C8") (pin "2") (pinfunction "2_2") (pintype "passive"))
      (node (ref "U1") (pin "2") (pinfunction "P0.00/XL1_2") (pintype "bidirectional"))
      (node (ref "XTAL2") (pin "2") (pinfunction "2_2") (pintype "passive"))
    )
    (net (code "80") (name "Net-(U1-P0.01{slash}XL2)") (class "Default")
      (node (ref "C13") (pin "2") (pinfunction "2_2") (pintype "passive"))
      (node (ref "U1") (pin "3") (pinfunction "P0.01/XL2_3") (pintype "bidirectional"))
      (node (ref "XTAL2") (pin "1") (pinfunction "1_1") (pintype "passive"))
    )
    (net (code "81") (name "Net-(U1-XC1)") (class "Default")
      (node (ref "C9") (pin "1") (pinfunction "1_1") (pintype "passive"))
      (node (ref "U1") (pin "34") (pinfunction "XC1_34") (pintype "input"))
      (node (ref "XTAL1") (pin "1") (pinfunction "1_1") (pintype "passive"))
    )
    (net (code "82") (name "Net-(U1-XC2)") (class "Default")
      (node (ref "C7") (pin "1") (pinfunction "1_1") (pintype "passive"))
      (node (ref "U1") (pin "35") (pinfunction "XC2_35") (pintype "output"))
      (node (ref "XTAL1") (pin "2") (pinfunction "2_2") (pintype "passive"))
    )
    (net (code "83") (name "VBAT") (class "Default")
      (node (ref "C35") (pin "2") (pinfunction "2_2") (pintype "passive"))
      (node (ref "D8") (pin "1") (pinfunction "BAT_1") (pintype "passive"))
      (node (ref "D9") (pin "2") (pinfunction "EN_2") (pintype "passive"))
      (node (ref "D9") (pin "7") (pinfunction "VIN_7") (pintype "passive"))
      (node (ref "P3") (pin "1") (pinfunction "1_1") (pintype "passive"))
    )
    (net (code "84") (name "unconnected-(D1-SS-Pad14)") (class "Default")
      (node (ref "D1") (pin "14") (pinfunction "SS_14") (pintype "passive"))
    )
    (net (code "85") (name "unconnected-(D2-NC-Pad6)") (class "Default")
      (node (ref "D2") (pin "6") (pinfunction "NC_6") (pintype "passive"))
    )
    (net (code "86") (name "unconnected-(D2-NC-Pad9)") (class "Default")
      (node (ref "D2") (pin "9") (pinfunction "NC_9") (pintype "passive"))
    )
    (net (code "87") (name "unconnected-(D3-ADC-Pad38)") (class "Default")
      (node (ref "D3") (pin "38") (pinfunction "ADC_38") (pintype "passive"))
    )
    (net (code "88") (name "unconnected-(D3-GPIO0-Pad10)") (class "Default")
      (node (ref "D3") (pin "10") (pinfunction "GPIO0_10") (pintype "passive"))
    )
    (net (code "89") (name "unconnected-(D3-GPIO1-Pad29)") (class "Default")
      (node (ref "D3") (pin "29") (pinfunction "GPIO1_29") (pintype "passive"))
    )
    (net (code "90") (name "unconnected-(D3-NC-Pad20)") (class "Default")
      (node (ref "D3") (pin "20") (pinfunction "NC_20") (pintype "passive"))
    )
    (net (code "91") (name "unconnected-(D3-NETLIGHT-Pad41)") (class "Default")
      (node (ref "D3") (pin "41") (pinfunction "NETLIGHT_41") (pintype "passive"))
    )
    (net (code "92") (name "unconnected-(D3-RTC_EINT-Pad12)") (class "Default")
      (node (ref "D3") (pin "12") (pinfunction "RTC_EINT_12") (pintype "passive"))
    )
    (net (code "93") (name "unconnected-(D3-RTC_GPIO0-Pad11)") (class "Default")
      (node (ref "D3") (pin "11") (pinfunction "RTC_GPIO0_11") (pintype "passive"))
    )
    (net (code "94") (name "unconnected-(D3-SIM_DET-Pad14)") (class "Default")
      (node (ref "D3") (pin "14") (pinfunction "SIM_DET_14") (pintype "passive"))
    )
    (net (code "95") (name "unconnected-(D3-UART1_CTS-Pad4)") (class "Default")
      (node (ref "D3") (pin "4") (pinfunction "UART1_CTS_4") (pintype "passive"))
    )
    (net (code "96") (name "unconnected-(D3-UART1_DCD-Pad5)") (class "Default")
      (node (ref "D3") (pin "5") (pinfunction "UART1_DCD_5") (pintype "passive"))
    )
    (net (code "97") (name "unconnected-(D3-UART1_RI-Pad7)") (class "Default")
      (node (ref "D3") (pin "7") (pinfunction "UART1_RI_7") (pintype "passive"))
    )
    (net (code "98") (name "unconnected-(D3-UART2_RXD-Pad23)") (class "Default")
      (node (ref "D3") (pin "23") (pinfunction "UART2_RXD_23") (pintype "passive"))
    )
    (net (code "99") (name "unconnected-(D3-UART2_TXD-Pad22)") (class "Default")
      (node (ref "D3") (pin "22") (pinfunction "UART2_TXD_22") (pintype "passive"))
    )
    (net (code "100") (name "unconnected-(D3-USB_DN-Pad26)") (class "Default")
      (node (ref "D3") (pin "26") (pinfunction "USB_DN_26") (pintype "passive"))
    )
    (net (code "101") (name "unconnected-(D3-USB_DP-Pad25)") (class "Default")
      (node (ref "D3") (pin "25") (pinfunction "USB_DP_25") (pintype "passive"))
    )
    (net (code "102") (name "unconnected-(D3-USB_VBUS-Pad24)") (class "Default")
      (node (ref "D3") (pin "24") (pinfunction "USB_VBUS_24") (pintype "passive"))
    )
    (net (code "103") (name "unconnected-(D3-VDD_3V3-Pad9)") (class "Default")
      (node (ref "D3") (pin "9") (pinfunction "VDD_3V3_9") (pintype "passive"))
    )
    (net (code "104") (name "unconnected-(D4-NC-Pad2)") (class "Default")
      (node (ref "D4") (pin "2") (pinfunction "NC_2") (pintype "passive"))
    )
    (net (code "105") (name "unconnected-(D4-NC-Pad4)") (class "Default")
      (node (ref "D4") (pin "4") (pinfunction "NC_4") (pintype "passive"))
    )
    (net (code "106") (name "unconnected-(D4-NC-Pad5)") (class "Default")
      (node (ref "D4") (pin "5") (pinfunction "NC_5") (pintype "passive"))
    )
    (net (code "107") (name "unconnected-(D6-PadAD-EN)") (class "Default")
      (node (ref "D6") (pin "AD-EN") (pinfunction "AD-EN_AD-EN") (pintype "passive"))
    )
    (net (code "108") (name "unconnected-(D6-PadEN1)") (class "Default")
      (node (ref "D6") (pin "EN1") (pinfunction "EN1_EN1") (pintype "passive"))
    )
    (net (code "109") (name "unconnected-(D6-PadEN2)") (class "Default")
      (node (ref "D6") (pin "EN2") (pinfunction "EN2_EN2") (pintype "passive"))
    )
    (net (code "110") (name "unconnected-(D8-CHRG-Pad3)") (class "Default")
      (node (ref "D8") (pin "3") (pinfunction "CHRG_3") (pintype "passive"))
    )
    (net (code "111") (name "unconnected-(D8-POWER_ON-Pad2)") (class "Default")
      (node (ref "D8") (pin "2") (pinfunction "POWER_ON_2") (pintype "passive"))
    )
    (net (code "112") (name "unconnected-(D9-NC-Pad3)") (class "Default")
      (node (ref "D9") (pin "3") (pinfunction "NC_3") (pintype "passive"))
    )
    (net (code "113") (name "unconnected-(U1-DCC-Pad47)") (class "Default")
      (node (ref "U1") (pin "47") (pinfunction "DCC_47") (pintype "output"))
    )
    (net (code "114") (name "unconnected-(U1-DEC2-Pad32)") (class "Default")
      (node (ref "U1") (pin "32") (pinfunction "DEC2_32") (pintype "power_in"))
    )
    (net (code "115") (name "unconnected-(U1-N.C.-Pad44)") (class "Default")
      (node (ref "U1") (pin "44") (pinfunction "N.C._44") (pintype "power_in"))
    )
  )
)
